# bump.net
KiCad netlist of a schematic drawn in EAGLE
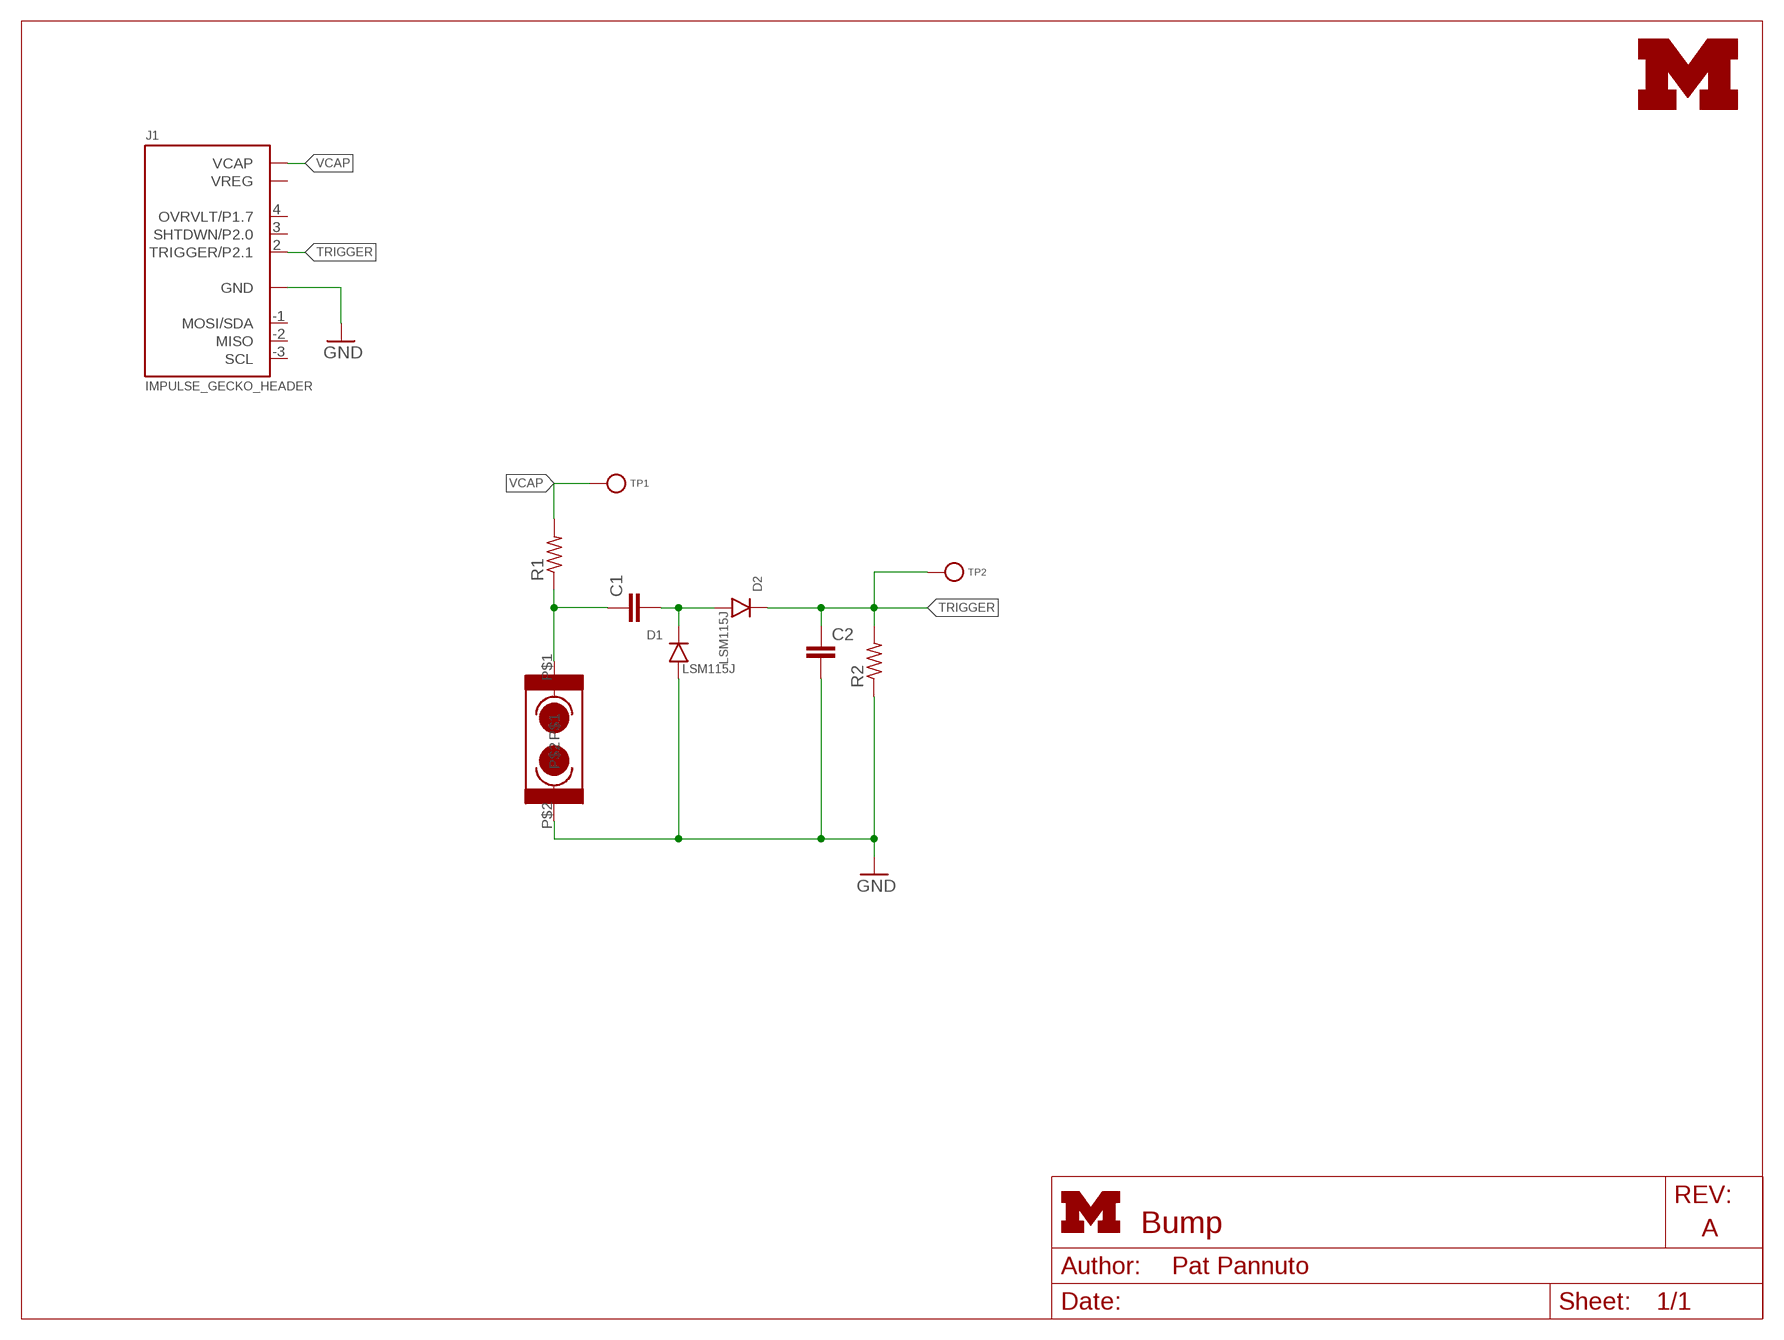
[diagram p0: schematic, sheet 1]

(export (version "E")
  (design (tool "Eeschema 10.0.6"))
  (components
    (comp (ref "C1")
      (value "C-EUC0603")
      (footprint "eagle-import:C0603")
      (libsource (lib "eagle-import") (part "C-EUC0603"))
    )
    (comp (ref "C2")
      (value "C-EUC0603")
      (footprint "eagle-import:C0603")
      (libsource (lib "eagle-import") (part "C-EUC0603"))
    )
    (comp (ref "D1")
      (value "LSM115J")
      (footprint "eagle-import:D0-214BA")
      (libsource (lib "eagle-import") (part "LSM115J"))
    )
    (comp (ref "D2")
      (value "LSM115J")
      (footprint "eagle-import:D0-214BA")
      (libsource (lib "eagle-import") (part "LSM115J"))
    )
    (comp (ref "J1")
      (value "IMPULSE_GECKO_HEADER")
      (footprint "eagle-import:HEADER1X9_0.05IN")
      (libsource (lib "eagle-import") (part "IMPULSE_GECKO_HEADER"))
    )
    (comp (ref "R1")
      (value "R-US_R0603")
      (footprint "eagle-import:R0603")
      (libsource (lib "eagle-import") (part "R-US_R0603"))
    )
    (comp (ref "R2")
      (value "R-US_R0603")
      (footprint "eagle-import:R0603")
      (libsource (lib "eagle-import") (part "R-US_R0603"))
    )
    (comp (ref "TP1")
      (value "TEST_POINT_0.040IN")
      (footprint "eagle-import:TESTPOINT_0.040IN")
      (libsource (lib "eagle-import") (part "TEST_POINT_0.040IN"))
    )
    (comp (ref "TP2")
      (value "TEST_POINT_0.040IN")
      (footprint "eagle-import:TESTPOINT_0.040IN")
      (libsource (lib "eagle-import") (part "TEST_POINT_0.040IN"))
    )
    (comp (ref "U$3")
      (value "UMICH_SOLID_SMALL+")
      (footprint "eagle-import:UMICH_SOLID_100MIL")
      (libsource (lib "eagle-import") (part "UMICH_SOLID_SMALL+"))
    )
    (comp (ref "VS1")
      (value "SQ-SEN-200")
      (footprint "eagle-import:SQ-SEN-200")
      (libsource (lib "eagle-import") (part "SQ-SEN-200"))
    )
  )
  (nets
    (net (code "1") (name "GND") (class "Default")
      (node (ref "C2") (pin "2") (pinfunction "2_2") (pintype "passive"))
      (node (ref "D1") (pin "A") (pinfunction "A_A") (pintype "bidirectional"))
      (node (ref "J1") (pin "0") (pinfunction "GND_0") (pintype "bidirectional"))
      (node (ref "R2") (pin "1") (pinfunction "1_1") (pintype "passive"))
      (node (ref "VS1") (pin "P$2") (pinfunction "P$2_P$2") (pintype "bidirectional"))
    )
    (net (code "2") (name "Net-(C1-Pad1)") (class "Default")
      (node (ref "C1") (pin "1") (pinfunction "1_1") (pintype "passive"))
      (node (ref "R1") (pin "1") (pinfunction "1_1") (pintype "passive"))
      (node (ref "VS1") (pin "P$1") (pinfunction "P$1_P$1") (pintype "bidirectional"))
    )
    (net (code "3") (name "Net-(C1-Pad2)") (class "Default")
      (node (ref "C1") (pin "2") (pinfunction "2_2") (pintype "passive"))
      (node (ref "D1") (pin "C") (pinfunction "C_C") (pintype "bidirectional"))
      (node (ref "D2") (pin "A") (pinfunction "A_A") (pintype "bidirectional"))
    )
    (net (code "4") (name "TRIGGER") (class "Default")
      (node (ref "C2") (pin "1") (pinfunction "1_1") (pintype "passive"))
      (node (ref "D2") (pin "C") (pinfunction "C_C") (pintype "bidirectional"))
      (node (ref "J1") (pin "2") (pinfunction "TRIGGER/P2.1_2") (pintype "bidirectional"))
      (node (ref "R2") (pin "2") (pinfunction "2_2") (pintype "passive"))
      (node (ref "TP2") (pin "TESTPOINT") (pinfunction "TESTPOINT_TESTPOINT") (pintype "bidirectional"))
    )
    (net (code "5") (name "VCAP") (class "Default")
      (node (ref "J1") (pin "5") (pinfunction "VCAP_5") (pintype "output"))
      (node (ref "R1") (pin "2") (pinfunction "2_2") (pintype "passive"))
      (node (ref "TP1") (pin "TESTPOINT") (pinfunction "TESTPOINT_TESTPOINT") (pintype "bidirectional"))
    )
    (net (code "6") (name "unconnected-(J1-MISO-Pad-2)") (class "Default")
      (node (ref "J1") (pin "-2") (pinfunction "MISO_-2") (pintype "bidirectional"))
    )
    (net (code "7") (name "unconnected-(J1-MOSI{slash}SDA-Pad-1)") (class "Default")
      (node (ref "J1") (pin "-1") (pinfunction "MOSI/SDA_-1") (pintype "bidirectional"))
    )
    (net (code "8") (name "unconnected-(J1-OVRVLT{slash}P1.7-Pad4)") (class "Default")
      (node (ref "J1") (pin "4") (pinfunction "OVRVLT/P1.7_4") (pintype "bidirectional"))
    )
    (net (code "9") (name "unconnected-(J1-SCL-Pad-3)") (class "Default")
      (node (ref "J1") (pin "-3") (pinfunction "SCL_-3") (pintype "bidirectional"))
    )
    (net (code "10") (name "unconnected-(J1-SHTDWN{slash}P2.0-Pad3)") (class "Default")
      (node (ref "J1") (pin "3") (pinfunction "SHTDWN/P2.0_3") (pintype "bidirectional"))
    )
    (net (code "11") (name "unconnected-(J1-VREG-Pad1)") (class "Default")
      (node (ref "J1") (pin "1") (pinfunction "VREG_1") (pintype "bidirectional"))
    )
  )
)
